# XBEE_BREAKOUT.net
KiCad netlist of a schematic drawn in Altium Designer
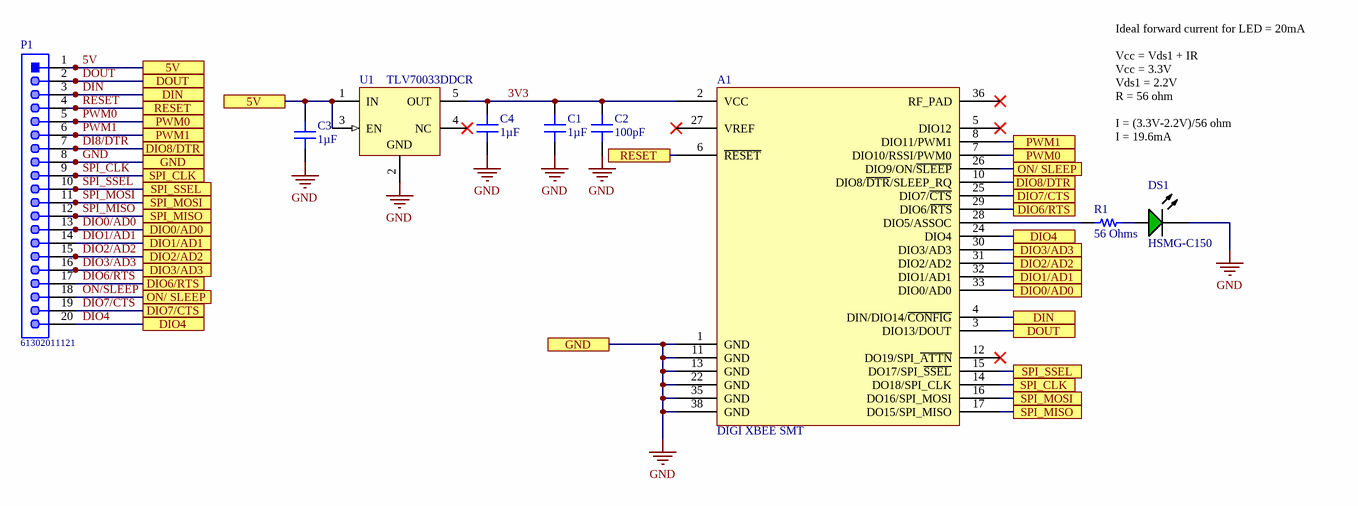
[diagram p0: XBEE_BREAKOUT.SchDoc]

(export (version "E")
  (design (tool "Eeschema 10.0.6"))
  (components
    (comp (ref "A1")
      (value "DIGI XBEE SMT")
      (footprint "*XCVR_XBP9X-DMUS-001")
      (libsource (lib "SCH - RF - MODULE - DIGI XBEE SMT") (part "DIGI XBEE SMT"))
    )
    (comp (ref "C1")
      (value "1µF")
      (footprint "CAP 0603_1608")
      (description "CAP CER 1UF 10V X7R 0603")
      (fields (field (name "PART NUMBER") "CC0603KRX7R6BB105") (field (name "MANUFACTURER") "Yageo"))
      (libsource (lib "Celestial Altium Library - altium_library") (part "Capacitor"))
    )
    (comp (ref "C2")
      (value "100pF")
      (footprint "CAP 0603_1608")
      (description "CAP CER 100PF 100V C0G/NP0 0603")
      (fields (field (name "PART NUMBER") "06031A101FAT2A") (field (name "MANUFACTURER") "AVX Corporation"))
      (libsource (lib "Celestial Altium Library - altium_library") (part "Capacitor"))
    )
    (comp (ref "C3")
      (value "1µF")
      (footprint "CAP 0603_1608")
      (description "CAP CER 1UF 10V X7R 0603")
      (fields (field (name "PART NUMBER") "CC0603KRX7R6BB105") (field (name "MANUFACTURER") "Yageo"))
      (libsource (lib "Celestial Altium Library - altium_library") (part "Capacitor"))
    )
    (comp (ref "C4")
      (value "1µF")
      (footprint "CAP 0603_1608")
      (description "CAP CER 1UF 10V X7R 0603")
      (fields (field (name "PART NUMBER") "CC0603KRX7R6BB105") (field (name "MANUFACTURER") "Yageo"))
      (libsource (lib "Celestial Altium Library - altium_library") (part "Capacitor"))
    )
    (comp (ref "DS1")
      (value "HSMG-C150")
      (footprint "AVAG-HSMX-C150_V")
      (description "Chip LED, Green, 65 mW, 25 mA, -40 to 85 degC, 2-Pin SMD, RoHS, Tape and Reel")
      (fields (field (name "MANUFACTURER") "Avago"))
      (libsource (lib "Altium Content Vault") (part "LED_GREEN_A1K2-2"))
    )
    (comp (ref "P1")
      (value "61302011121")
      (footprint "61302011121")
      (description "THT Vertical Pin Header WR-PHD, Pitch 2.54 mm, Single Row, 20 pins")
      (fields (field (name "MANUFACTURER") "Wurth Elektronik") (field (name "PUBLISHER") "WurthElektronik"))
      (libsource (lib "Altium Content Vault") (part "WE-CN-1P-M-R20"))
    )
    (comp (ref "R1")
      (value "56 Ohms")
      (footprint "RES 1206_3216")
      (description "RES SMD 56 OHM 1% 1/4W 1206")
      (fields (field (name "PART NUMBER") "CR1206-FX-56R0ELF") (field (name "MANUFACTURER") "Bourns Inc."))
      (libsource (lib "Celestial Altium Library - altium_library") (part "Resistor"))
    )
    (comp (ref "U1")
      (value "TLV70033DDCR")
      (footprint "DDC0005A_M")
      (fields (field (name "MANUFACTURER") "Texas Instruments"))
      (libsource (lib "Altium Content Vault") (part "TI-TXX7XXXX-5"))
    )
  )
  (nets
    (net (code "1") (name "/3V3") (class "Default")
      (node (ref "A1") (pin "2") (pinfunction "VCC_2") (pintype "passive"))
      (node (ref "C1") (pin "2") (pinfunction "2_2") (pintype "passive"))
      (node (ref "C2") (pin "2") (pinfunction "2_2") (pintype "passive"))
      (node (ref "C4") (pin "2") (pinfunction "2_2") (pintype "passive"))
      (node (ref "U1") (pin "5") (pinfunction "OUT_5") (pintype "power_in"))
    )
    (net (code "2") (name "/5V") (class "Default")
      (node (ref "C3") (pin "2") (pinfunction "2_2") (pintype "passive"))
      (node (ref "P1") (pin "1") (pinfunction "1_1") (pintype "passive"))
      (node (ref "U1") (pin "1") (pinfunction "IN_1") (pintype "power_in"))
      (node (ref "U1") (pin "3") (pinfunction "EN_3") (pintype "input"))
    )
    (net (code "3") (name "/DI8{slash}DTR") (class "Default")
      (node (ref "A1") (pin "10") (pinfunction "DIO8/~{DTR}/SLEEP_RQ_10") (pintype "passive"))
      (node (ref "P1") (pin "7") (pinfunction "7_7") (pintype "passive"))
    )
    (net (code "4") (name "/DIN") (class "Default")
      (node (ref "A1") (pin "4") (pinfunction "DIN/DIO14/~{CONFIG}_4") (pintype "passive"))
      (node (ref "P1") (pin "3") (pinfunction "3_3") (pintype "passive"))
    )
    (net (code "5") (name "/DIO0{slash}AD0") (class "Default")
      (node (ref "A1") (pin "33") (pinfunction "DIO0/AD0_33") (pintype "passive"))
      (node (ref "P1") (pin "13") (pinfunction "13_13") (pintype "passive"))
    )
    (net (code "6") (name "/DIO1{slash}AD1") (class "Default")
      (node (ref "A1") (pin "32") (pinfunction "DIO1/AD1_32") (pintype "passive"))
      (node (ref "P1") (pin "14") (pinfunction "14_14") (pintype "passive"))
    )
    (net (code "7") (name "/DIO2{slash}AD2") (class "Default")
      (node (ref "A1") (pin "31") (pinfunction "DIO2/AD2_31") (pintype "passive"))
      (node (ref "P1") (pin "15") (pinfunction "15_15") (pintype "passive"))
    )
    (net (code "8") (name "/DIO3{slash}AD3") (class "Default")
      (node (ref "A1") (pin "30") (pinfunction "DIO3/AD3_30") (pintype "passive"))
      (node (ref "P1") (pin "16") (pinfunction "16_16") (pintype "passive"))
    )
    (net (code "9") (name "/DIO4") (class "Default")
      (node (ref "A1") (pin "24") (pinfunction "DIO4_24") (pintype "passive"))
      (node (ref "P1") (pin "20") (pinfunction "20_20") (pintype "passive"))
    )
    (net (code "10") (name "/DIO6{slash}RTS") (class "Default")
      (node (ref "A1") (pin "29") (pinfunction "DIO6/~{RTS}_29") (pintype "passive"))
      (node (ref "P1") (pin "17") (pinfunction "17_17") (pintype "passive"))
    )
    (net (code "11") (name "/DIO7{slash}CTS") (class "Default")
      (node (ref "A1") (pin "25") (pinfunction "DIO7/~{CTS}_25") (pintype "passive"))
      (node (ref "P1") (pin "19") (pinfunction "19_19") (pintype "passive"))
    )
    (net (code "12") (name "/DOUT") (class "Default")
      (node (ref "A1") (pin "3") (pinfunction "DIO13/DOUT_3") (pintype "passive"))
      (node (ref "P1") (pin "2") (pinfunction "2_2") (pintype "passive"))
    )
    (net (code "13") (name "/ON{slash}SLEEP") (class "Default")
      (node (ref "A1") (pin "26") (pinfunction "DIO9/ON/~{SLEEP}_26") (pintype "passive"))
      (node (ref "P1") (pin "18") (pinfunction "18_18") (pintype "passive"))
    )
    (net (code "14") (name "/PWM0") (class "Default")
      (node (ref "A1") (pin "7") (pinfunction "DIO10/RSSI/PWM0_7") (pintype "passive"))
      (node (ref "P1") (pin "5") (pinfunction "5_5") (pintype "passive"))
    )
    (net (code "15") (name "/PWM1") (class "Default")
      (node (ref "A1") (pin "8") (pinfunction "DIO11/PWM1_8") (pintype "passive"))
      (node (ref "P1") (pin "6") (pinfunction "6_6") (pintype "passive"))
    )
    (net (code "16") (name "/RESET") (class "Default")
      (node (ref "A1") (pin "6") (pinfunction "~{RESET}_6") (pintype "passive"))
      (node (ref "P1") (pin "4") (pinfunction "4_4") (pintype "passive"))
    )
    (net (code "17") (name "/SPI_CLK") (class "Default")
      (node (ref "A1") (pin "14") (pinfunction "DO18/SPI_CLK_14") (pintype "passive"))
      (node (ref "P1") (pin "9") (pinfunction "9_9") (pintype "passive"))
    )
    (net (code "18") (name "/SPI_MISO") (class "Default")
      (node (ref "A1") (pin "17") (pinfunction "DO15/SPI_MISO_17") (pintype "passive"))
      (node (ref "P1") (pin "12") (pinfunction "12_12") (pintype "passive"))
    )
    (net (code "19") (name "/SPI_MOSI") (class "Default")
      (node (ref "A1") (pin "16") (pinfunction "DO16/SPI_MOSI_16") (pintype "passive"))
      (node (ref "P1") (pin "11") (pinfunction "11_11") (pintype "passive"))
    )
    (net (code "20") (name "/SPI_SSEL") (class "Default")
      (node (ref "A1") (pin "15") (pinfunction "DO17/SPI_~{SSEL}_15") (pintype "passive"))
      (node (ref "P1") (pin "10") (pinfunction "10_10") (pintype "passive"))
    )
    (net (code "21") (name "GND") (class "Default")
      (node (ref "A1") (pin "1") (pinfunction "GND_1") (pintype "passive"))
      (node (ref "A1") (pin "11") (pinfunction "GND_11") (pintype "passive"))
      (node (ref "A1") (pin "13") (pinfunction "GND_13") (pintype "passive"))
      (node (ref "A1") (pin "22") (pinfunction "GND_22") (pintype "passive"))
      (node (ref "A1") (pin "35") (pinfunction "GND_35") (pintype "passive"))
      (node (ref "A1") (pin "38") (pinfunction "GND_38") (pintype "passive"))
      (node (ref "C1") (pin "1") (pinfunction "1_1") (pintype "passive"))
      (node (ref "C2") (pin "1") (pinfunction "1_1") (pintype "passive"))
      (node (ref "C3") (pin "1") (pinfunction "1_1") (pintype "passive"))
      (node (ref "C4") (pin "1") (pinfunction "1_1") (pintype "passive"))
      (node (ref "DS1") (pin "2") (pinfunction "K_2") (pintype "passive"))
      (node (ref "P1") (pin "8") (pinfunction "8_8") (pintype "passive"))
      (node (ref "U1") (pin "2") (pinfunction "GND_2") (pintype "power_in"))
    )
    (net (code "22") (name "Net-(A1-DIO5{slash}ASSOC)") (class "Default")
      (node (ref "A1") (pin "28") (pinfunction "DIO5/ASSOC_28") (pintype "passive"))
      (node (ref "R1") (pin "1") (pinfunction "1_1") (pintype "passive"))
    )
    (net (code "23") (name "Net-(DS1-A)") (class "Default")
      (node (ref "DS1") (pin "1") (pinfunction "A_1") (pintype "passive"))
      (node (ref "R1") (pin "2") (pinfunction "2_2") (pintype "passive"))
    )
    (net (code "24") (name "unconnected-(A1-DIO12-Pad5)") (class "Default")
      (node (ref "A1") (pin "5") (pinfunction "DIO12_5") (pintype "passive+no_connect"))
    )
    (net (code "25") (name "unconnected-(A1-DO19{slash}SPI_~{ATTN}-Pad12)") (class "Default")
      (node (ref "A1") (pin "12") (pinfunction "DO19/SPI_~{ATTN}_12") (pintype "passive+no_connect"))
    )
    (net (code "26") (name "unconnected-(A1-RF_PAD-Pad36)") (class "Default")
      (node (ref "A1") (pin "36") (pinfunction "RF_PAD_36") (pintype "passive+no_connect"))
    )
    (net (code "27") (name "unconnected-(A1-VREF-Pad27)") (class "Default")
      (node (ref "A1") (pin "27") (pinfunction "VREF_27") (pintype "passive+no_connect"))
    )
    (net (code "28") (name "unconnected-(U1-NC-Pad4)") (class "Default")
      (node (ref "U1") (pin "4") (pinfunction "NC_4") (pintype "passive+no_connect"))
    )
  )
)
